# led_pack.net
KiCad netlist of a schematic drawn in Altium Designer
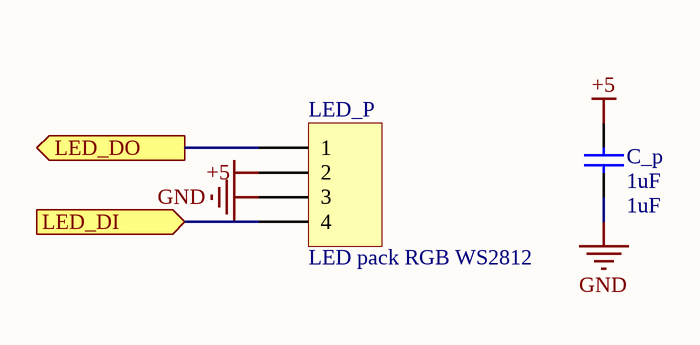
[diagram p0: led_pack.SchDoc]

(export (version "E")
  (design (tool "Eeschema 10.0.6"))
  (components
    (comp (ref "C_p")
      (value "1uF")
      (footprint "0603C")
      (description "CAP SMD 0603")
      (fields (field (name "ALTIUM_VALUE") "1uF") (field (name "PUBLISHER") "Altium Limited"))
      (libsource (lib "Miscellaneous Devices") (part "Cap"))
    )
    (comp (ref "LED_P")
      (value "LED pack RGB WS2812")
      (footprint "LED_PAKC_7")
      (description "7led-red white LED pack")
      (fields (field (name "PUBLISHER") "Altium Limited"))
      (libsource (lib "Altium") (part "Header 4"))
    )
  )
  (nets
    (net (code "1") (name "+5") (class "Default")
      (node (ref "C_p") (pin "2") (pinfunction "2_2") (pintype "passive"))
      (node (ref "LED_P") (pin "2") (pinfunction "2_2") (pintype "passive"))
    )
    (net (code "2") (name "/LED_DI") (class "Default")
      (node (ref "LED_P") (pin "4") (pinfunction "4_4") (pintype "passive"))
    )
    (net (code "3") (name "/LED_DO") (class "Default")
      (node (ref "LED_P") (pin "1") (pinfunction "1_1") (pintype "passive"))
    )
    (net (code "4") (name "GND") (class "Default")
      (node (ref "C_p") (pin "1") (pinfunction "1_1") (pintype "passive"))
      (node (ref "LED_P") (pin "3") (pinfunction "3_3") (pintype "passive"))
    )
  )
)
